# Ffrydiau_controls.net
KiCad netlist of a schematic drawn in EAGLE
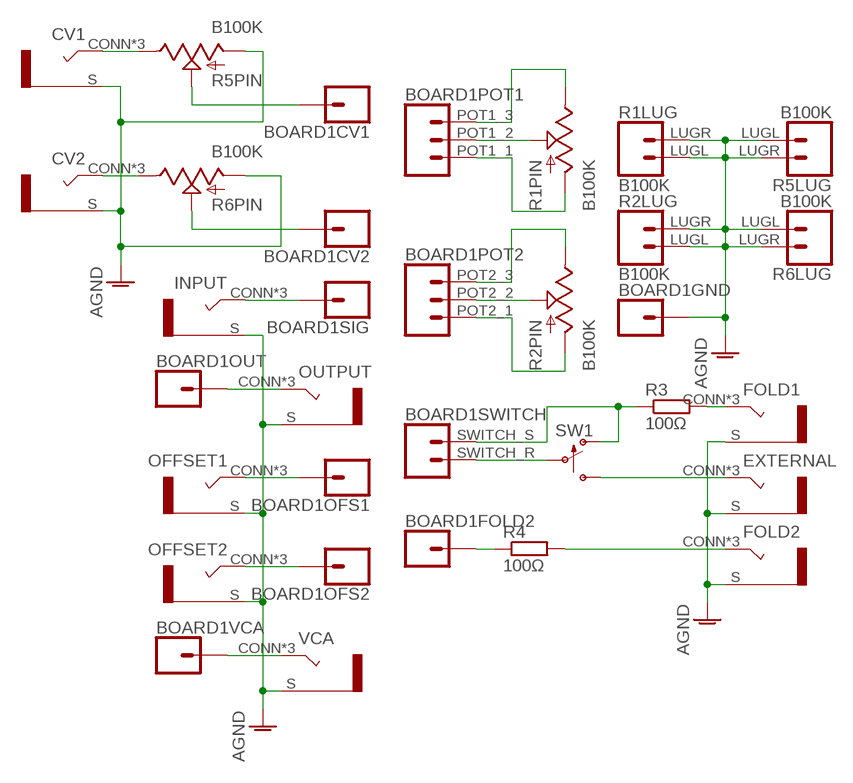
[diagram p0: schematic, sheet 1]

(export (version "E")
  (design (tool "Eeschema 10.0.6"))
  (components
    (comp (ref "BOARD1")
      (value "FFRYDIAU_LINK")
      (footprint "eagle-import:FFRYDIAU")
      (libsource (lib "eagle-import") (part "FFRYDIAU_LINK"))
    )
    (comp (ref "CV1")
      (value "COMBI-JACKCINCHNANA")
      (footprint "eagle-import:NEWCOMBOJACK_PANEL")
      (libsource (lib "eagle-import") (part "COMBI-JACKCINCHNANA"))
    )
    (comp (ref "CV2")
      (value "COMBI-JACKCINCHNANA")
      (footprint "eagle-import:NEWCOMBOJACK_PANEL")
      (libsource (lib "eagle-import") (part "COMBI-JACKCINCHNANA"))
    )
    (comp (ref "EXTERNAL")
      (value "COMBI-JACKCINCHNANA")
      (footprint "eagle-import:NEWCOMBOJACK_PANEL")
      (libsource (lib "eagle-import") (part "COMBI-JACKCINCHNANA"))
    )
    (comp (ref "FOLD1")
      (value "COMBI-JACKCINCHNANA")
      (footprint "eagle-import:NEWCOMBOJACK_PANEL")
      (libsource (lib "eagle-import") (part "COMBI-JACKCINCHNANA"))
    )
    (comp (ref "FOLD2")
      (value "COMBI-JACKCINCHNANA")
      (footprint "eagle-import:NEWCOMBOJACK_PANEL")
      (libsource (lib "eagle-import") (part "COMBI-JACKCINCHNANA"))
    )
    (comp (ref "INPUT")
      (value "COMBI-JACKCINCHNANA")
      (footprint "eagle-import:NEWCOMBOJACK_PANEL")
      (libsource (lib "eagle-import") (part "COMBI-JACKCINCHNANA"))
    )
    (comp (ref "OFFSET1")
      (value "COMBI-JACKCINCHNANA")
      (footprint "eagle-import:NEWCOMBOJACK_PANEL")
      (libsource (lib "eagle-import") (part "COMBI-JACKCINCHNANA"))
    )
    (comp (ref "OFFSET2")
      (value "COMBI-JACKCINCHNANA")
      (footprint "eagle-import:NEWCOMBOJACK_PANEL")
      (libsource (lib "eagle-import") (part "COMBI-JACKCINCHNANA"))
    )
    (comp (ref "OUTPUT")
      (value "COMBI-JACKCINCHNANA")
      (footprint "eagle-import:NEWCOMBOJACK_PANEL")
      (libsource (lib "eagle-import") (part "COMBI-JACKCINCHNANA"))
    )
    (comp (ref "R1")
      (value "B100K")
      (footprint "eagle-import:ALPHA_RV09_9MMPOT")
      (libsource (lib "eagle-import") (part "POTENTIOMETER"))
    )
    (comp (ref "R2")
      (value "B100K")
      (footprint "eagle-import:ALPHA_RV09_9MMPOT")
      (libsource (lib "eagle-import") (part "POTENTIOMETER"))
    )
    (comp (ref "R3")
      (value "100Ω")
      (footprint "eagle-import:0207_10")
      (libsource (lib "eagle-import") (part "R-EU_0207/10"))
    )
    (comp (ref "R4")
      (value "100Ω")
      (footprint "eagle-import:0207_10")
      (libsource (lib "eagle-import") (part "R-EU_0207/10"))
    )
    (comp (ref "R5")
      (value "B100K")
      (footprint "eagle-import:ALPHA_RV09_9MMPOT")
      (libsource (lib "eagle-import") (part "POTENTIOMETER"))
    )
    (comp (ref "R6")
      (value "B100K")
      (footprint "eagle-import:ALPHA_RV09_9MMPOT")
      (libsource (lib "eagle-import") (part "POTENTIOMETER"))
    )
    (comp (ref "SW1")
      (value "SPDT_SWITCHDW1")
      (footprint "eagle-import:MICRODPDT-DW1")
      (libsource (lib "eagle-import") (part "SPDT_SWITCHDW1"))
    )
    (comp (ref "VCA")
      (value "COMBI-JACKCINCHNANA")
      (footprint "eagle-import:NEWCOMBOJACK_PANEL")
      (libsource (lib "eagle-import") (part "COMBI-JACKCINCHNANA"))
    )
  )
  (nets
    (net (code "1") (name "AGND") (class "Default")
      (node (ref "BOARD1") (pin "GND") (pinfunction "1_GND") (pintype "passive"))
      (node (ref "CV1") (pin "S") (pinfunction "S_S") (pintype "passive"))
      (node (ref "CV2") (pin "S") (pinfunction "S_S") (pintype "passive"))
      (node (ref "EXTERNAL") (pin "S") (pinfunction "S_S") (pintype "passive"))
      (node (ref "FOLD1") (pin "S") (pinfunction "S_S") (pintype "passive"))
      (node (ref "FOLD2") (pin "S") (pinfunction "S_S") (pintype "passive"))
      (node (ref "INPUT") (pin "S") (pinfunction "S_S") (pintype "passive"))
      (node (ref "OFFSET1") (pin "S") (pinfunction "S_S") (pintype "passive"))
      (node (ref "OFFSET2") (pin "S") (pinfunction "S_S") (pintype "passive"))
      (node (ref "OUTPUT") (pin "S") (pinfunction "S_S") (pintype "passive"))
      (node (ref "R1") (pin "LUGL") (pinfunction "1_LUGL") (pintype "passive"))
      (node (ref "R1") (pin "LUGR") (pinfunction "2_LUGR") (pintype "passive"))
      (node (ref "R2") (pin "LUGL") (pinfunction "1_LUGL") (pintype "passive"))
      (node (ref "R2") (pin "LUGR") (pinfunction "2_LUGR") (pintype "passive"))
      (node (ref "R5") (pin "C1") (pinfunction "A_C1") (pintype "passive"))
      (node (ref "R5") (pin "LUGL") (pinfunction "1_LUGL") (pintype "passive"))
      (node (ref "R5") (pin "LUGR") (pinfunction "2_LUGR") (pintype "passive"))
      (node (ref "R6") (pin "C1") (pinfunction "A_C1") (pintype "passive"))
      (node (ref "R6") (pin "LUGL") (pinfunction "1_LUGL") (pintype "passive"))
      (node (ref "R6") (pin "LUGR") (pinfunction "2_LUGR") (pintype "passive"))
      (node (ref "VCA") (pin "S") (pinfunction "S_S") (pintype "passive"))
    )
    (net (code "2") (name "Net-(BOARD1A-1)") (class "Default")
      (node (ref "BOARD1") (pin "CV1") (pinfunction "1_CV1") (pintype "passive"))
      (node (ref "R5") (pin "C2") (pinfunction "W_C2") (pintype "passive"))
    )
    (net (code "3") (name "Net-(BOARD1B-1)") (class "Default")
      (node (ref "BOARD1") (pin "CV2") (pinfunction "1_CV2") (pintype "passive"))
      (node (ref "R6") (pin "C2") (pinfunction "W_C2") (pintype "passive"))
    )
    (net (code "4") (name "Net-(BOARD1C-1)") (class "Default")
      (node (ref "BOARD1") (pin "FOLD2") (pinfunction "1_FOLD2") (pintype "passive"))
      (node (ref "R4") (pin "1") (pinfunction "1_1") (pintype "passive"))
    )
    (net (code "5") (name "Net-(BOARD1E-1)") (class "Default")
      (node (ref "BOARD1") (pin "OFS1") (pinfunction "1_OFS1") (pintype "passive"))
      (node (ref "OFFSET1") (pin "CONN") (pinfunction "T_CONN") (pintype "passive"))
      (node (ref "OFFSET1") (pin "T1") (pinfunction "T_T1") (pintype "passive"))
      (node (ref "OFFSET1") (pin "T2") (pinfunction "T_T2") (pintype "passive"))
    )
    (net (code "6") (name "Net-(BOARD1F-1)") (class "Default")
      (node (ref "BOARD1") (pin "OFS2") (pinfunction "1_OFS2") (pintype "passive"))
      (node (ref "OFFSET2") (pin "CONN") (pinfunction "T_CONN") (pintype "passive"))
      (node (ref "OFFSET2") (pin "T1") (pinfunction "T_T1") (pintype "passive"))
      (node (ref "OFFSET2") (pin "T2") (pinfunction "T_T2") (pintype "passive"))
    )
    (net (code "7") (name "Net-(BOARD1G-1)") (class "Default")
      (node (ref "BOARD1") (pin "OUT") (pinfunction "1_OUT") (pintype "passive"))
      (node (ref "OUTPUT") (pin "CONN") (pinfunction "T_CONN") (pintype "passive"))
      (node (ref "OUTPUT") (pin "T1") (pinfunction "T_T1") (pintype "passive"))
      (node (ref "OUTPUT") (pin "T2") (pinfunction "T_T2") (pintype "passive"))
    )
    (net (code "8") (name "Net-(BOARD1H-1)") (class "Default")
      (node (ref "BOARD1") (pin "POT1_1") (pinfunction "1_POT1_1") (pintype "passive"))
      (node (ref "R1") (pin "C1") (pinfunction "A_C1") (pintype "passive"))
    )
    (net (code "9") (name "Net-(BOARD1H-2)") (class "Default")
      (node (ref "BOARD1") (pin "POT1_2") (pinfunction "2_POT1_2") (pintype "passive"))
      (node (ref "R1") (pin "C2") (pinfunction "W_C2") (pintype "passive"))
    )
    (net (code "10") (name "Net-(BOARD1H-3)") (class "Default")
      (node (ref "BOARD1") (pin "POT1_3") (pinfunction "3_POT1_3") (pintype "passive"))
      (node (ref "R1") (pin "C3") (pinfunction "B_C3") (pintype "passive"))
    )
    (net (code "11") (name "Net-(BOARD1I-1)") (class "Default")
      (node (ref "BOARD1") (pin "POT2_1") (pinfunction "1_POT2_1") (pintype "passive"))
      (node (ref "R2") (pin "C1") (pinfunction "A_C1") (pintype "passive"))
    )
    (net (code "12") (name "Net-(BOARD1I-2)") (class "Default")
      (node (ref "BOARD1") (pin "POT2_2") (pinfunction "2_POT2_2") (pintype "passive"))
      (node (ref "R2") (pin "C2") (pinfunction "W_C2") (pintype "passive"))
    )
    (net (code "13") (name "Net-(BOARD1I-3)") (class "Default")
      (node (ref "BOARD1") (pin "POT2_3") (pinfunction "3_POT2_3") (pintype "passive"))
      (node (ref "R2") (pin "C3") (pinfunction "B_C3") (pintype "passive"))
    )
    (net (code "14") (name "Net-(BOARD1J-1)") (class "Default")
      (node (ref "BOARD1") (pin "SIG") (pinfunction "1_SIG") (pintype "passive"))
      (node (ref "INPUT") (pin "CONN") (pinfunction "T_CONN") (pintype "passive"))
      (node (ref "INPUT") (pin "T1") (pinfunction "T_T1") (pintype "passive"))
      (node (ref "INPUT") (pin "T2") (pinfunction "T_T2") (pintype "passive"))
    )
    (net (code "15") (name "Net-(BOARD1K-1)") (class "Default")
      (node (ref "BOARD1") (pin "SWITCH_R") (pinfunction "1_SWITCH_R") (pintype "passive"))
      (node (ref "SW1") (pin "C2") (pinfunction "P_C2") (pintype "passive"))
    )
    (net (code "16") (name "Net-(BOARD1K-2)") (class "Default")
      (node (ref "BOARD1") (pin "SWITCH_S") (pinfunction "2_SWITCH_S") (pintype "passive"))
      (node (ref "R3") (pin "1") (pinfunction "1_1") (pintype "passive"))
      (node (ref "SW1") (pin "C1") (pinfunction "O_C1") (pintype "passive"))
    )
    (net (code "17") (name "Net-(BOARD1L-1)") (class "Default")
      (node (ref "BOARD1") (pin "VCA") (pinfunction "1_VCA") (pintype "passive"))
      (node (ref "VCA") (pin "CONN") (pinfunction "T_CONN") (pintype "passive"))
      (node (ref "VCA") (pin "T1") (pinfunction "T_T1") (pintype "passive"))
      (node (ref "VCA") (pin "T2") (pinfunction "T_T2") (pintype "passive"))
    )
    (net (code "18") (name "Net-(FOLD1-T-PadCONN)") (class "Default")
      (node (ref "FOLD1") (pin "CONN") (pinfunction "T_CONN") (pintype "passive"))
      (node (ref "FOLD1") (pin "T1") (pinfunction "T_T1") (pintype "passive"))
      (node (ref "FOLD1") (pin "T2") (pinfunction "T_T2") (pintype "passive"))
      (node (ref "R3") (pin "2") (pinfunction "2_2") (pintype "passive"))
    )
    (net (code "19") (name "Net-(FOLD2-T-PadCONN)") (class "Default")
      (node (ref "FOLD2") (pin "CONN") (pinfunction "T_CONN") (pintype "passive"))
      (node (ref "FOLD2") (pin "T1") (pinfunction "T_T1") (pintype "passive"))
      (node (ref "FOLD2") (pin "T2") (pinfunction "T_T2") (pintype "passive"))
      (node (ref "R4") (pin "2") (pinfunction "2_2") (pintype "passive"))
    )
    (net (code "20") (name "Net-(R5B-B)") (class "Default")
      (node (ref "CV1") (pin "CONN") (pinfunction "T_CONN") (pintype "passive"))
      (node (ref "CV1") (pin "T1") (pinfunction "T_T1") (pintype "passive"))
      (node (ref "CV1") (pin "T2") (pinfunction "T_T2") (pintype "passive"))
      (node (ref "R5") (pin "C3") (pinfunction "B_C3") (pintype "passive"))
    )
    (net (code "21") (name "Net-(R6B-B)") (class "Default")
      (node (ref "CV2") (pin "CONN") (pinfunction "T_CONN") (pintype "passive"))
      (node (ref "CV2") (pin "T1") (pinfunction "T_T1") (pintype "passive"))
      (node (ref "CV2") (pin "T2") (pinfunction "T_T2") (pintype "passive"))
      (node (ref "R6") (pin "C3") (pinfunction "B_C3") (pintype "passive"))
    )
    (net (code "22") (name "Net-(SW1-S)") (class "Default")
      (node (ref "EXTERNAL") (pin "CONN") (pinfunction "T_CONN") (pintype "passive"))
      (node (ref "EXTERNAL") (pin "T1") (pinfunction "T_T1") (pintype "passive"))
      (node (ref "EXTERNAL") (pin "T2") (pinfunction "T_T2") (pintype "passive"))
      (node (ref "SW1") (pin "C3") (pinfunction "S_C3") (pintype "passive"))
    )
  )
)
